# sheet.net
KiCad netlist of a schematic drawn in Altium Designer
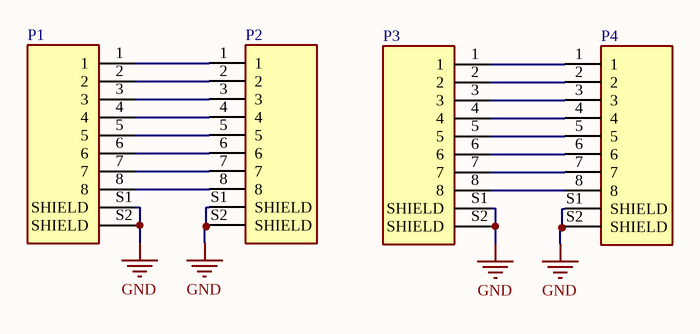
[diagram p0: sheet.SchDoc]

(export (version "E")
  (design (tool "Eeschema 10.0.6"))
  (components
    (comp (ref "P1")
      (value "1-406541-5")
      (footprint "TE_1-406541-5")
      (description "Conn RJ-45 F 8 POS 2.04mm Solder RA Thru-Hole 8 Terminal 1 Port Cat 5 Box/Tray")
      (fields (field (name "MF") "{'manufacturer': u'TE Connectivity'}"))
      (libsource (lib "1-406541-5") (part "1-406541-5"))
    )
    (comp (ref "P2")
      (value "1-406541-5")
      (footprint "TE_1-406541-5")
      (description "Conn RJ-45 F 8 POS 2.04mm Solder RA Thru-Hole 8 Terminal 1 Port Cat 5 Box/Tray")
      (fields (field (name "MF") "{'manufacturer': u'TE Connectivity'}"))
      (libsource (lib "") (part "1-406541-5_1"))
    )
    (comp (ref "P3")
      (value "1-406541-5")
      (footprint "TE_1-406541-5")
      (description "Conn RJ-45 F 8 POS 2.04mm Solder RA Thru-Hole 8 Terminal 1 Port Cat 5 Box/Tray")
      (fields (field (name "MF") "{'manufacturer': u'TE Connectivity'}"))
      (libsource (lib "1-406541-5") (part "1-406541-5"))
    )
    (comp (ref "P4")
      (value "1-406541-5")
      (footprint "TE_1-406541-5")
      (description "Conn RJ-45 F 8 POS 2.04mm Solder RA Thru-Hole 8 Terminal 1 Port Cat 5 Box/Tray")
      (fields (field (name "MF") "{'manufacturer': u'TE Connectivity'}"))
      (libsource (lib "") (part "1-406541-5_1"))
    )
  )
  (nets
    (net (code "1") (name "GND") (class "Default")
      (node (ref "P1") (pin "S1") (pinfunction "SHIELD_S1") (pintype "passive"))
      (node (ref "P1") (pin "S2") (pinfunction "SHIELD_S2") (pintype "passive"))
      (node (ref "P2") (pin "S1") (pinfunction "SHIELD_S1") (pintype "passive"))
      (node (ref "P2") (pin "S2") (pinfunction "SHIELD_S2") (pintype "passive"))
      (node (ref "P3") (pin "S1") (pinfunction "SHIELD_S1") (pintype "passive"))
      (node (ref "P3") (pin "S2") (pinfunction "SHIELD_S2") (pintype "passive"))
      (node (ref "P4") (pin "S1") (pinfunction "SHIELD_S1") (pintype "passive"))
      (node (ref "P4") (pin "S2") (pinfunction "SHIELD_S2") (pintype "passive"))
    )
    (net (code "2") (name "Net-(P1-Pad1)") (class "Default")
      (node (ref "P1") (pin "1") (pinfunction "1_1") (pintype "passive"))
      (node (ref "P2") (pin "1") (pinfunction "1_1") (pintype "passive"))
    )
    (net (code "3") (name "Net-(P1-Pad2)") (class "Default")
      (node (ref "P1") (pin "2") (pinfunction "2_2") (pintype "passive"))
      (node (ref "P2") (pin "2") (pinfunction "2_2") (pintype "passive"))
    )
    (net (code "4") (name "Net-(P1-Pad3)") (class "Default")
      (node (ref "P1") (pin "3") (pinfunction "3_3") (pintype "passive"))
      (node (ref "P2") (pin "3") (pinfunction "3_3") (pintype "passive"))
    )
    (net (code "5") (name "Net-(P1-Pad4)") (class "Default")
      (node (ref "P1") (pin "4") (pinfunction "4_4") (pintype "passive"))
      (node (ref "P2") (pin "4") (pinfunction "4_4") (pintype "passive"))
    )
    (net (code "6") (name "Net-(P1-Pad5)") (class "Default")
      (node (ref "P1") (pin "5") (pinfunction "5_5") (pintype "passive"))
      (node (ref "P2") (pin "5") (pinfunction "5_5") (pintype "passive"))
    )
    (net (code "7") (name "Net-(P1-Pad6)") (class "Default")
      (node (ref "P1") (pin "6") (pinfunction "6_6") (pintype "passive"))
      (node (ref "P2") (pin "6") (pinfunction "6_6") (pintype "passive"))
    )
    (net (code "8") (name "Net-(P1-Pad7)") (class "Default")
      (node (ref "P1") (pin "7") (pinfunction "7_7") (pintype "passive"))
      (node (ref "P2") (pin "7") (pinfunction "7_7") (pintype "passive"))
    )
    (net (code "9") (name "Net-(P1-Pad8)") (class "Default")
      (node (ref "P1") (pin "8") (pinfunction "8_8") (pintype "passive"))
      (node (ref "P2") (pin "8") (pinfunction "8_8") (pintype "passive"))
    )
    (net (code "10") (name "Net-(P3-Pad1)") (class "Default")
      (node (ref "P3") (pin "1") (pinfunction "1_1") (pintype "passive"))
      (node (ref "P4") (pin "1") (pinfunction "1_1") (pintype "passive"))
    )
    (net (code "11") (name "Net-(P3-Pad2)") (class "Default")
      (node (ref "P3") (pin "2") (pinfunction "2_2") (pintype "passive"))
      (node (ref "P4") (pin "2") (pinfunction "2_2") (pintype "passive"))
    )
    (net (code "12") (name "Net-(P3-Pad3)") (class "Default")
      (node (ref "P3") (pin "3") (pinfunction "3_3") (pintype "passive"))
      (node (ref "P4") (pin "3") (pinfunction "3_3") (pintype "passive"))
    )
    (net (code "13") (name "Net-(P3-Pad4)") (class "Default")
      (node (ref "P3") (pin "4") (pinfunction "4_4") (pintype "passive"))
      (node (ref "P4") (pin "4") (pinfunction "4_4") (pintype "passive"))
    )
    (net (code "14") (name "Net-(P3-Pad5)") (class "Default")
      (node (ref "P3") (pin "5") (pinfunction "5_5") (pintype "passive"))
      (node (ref "P4") (pin "5") (pinfunction "5_5") (pintype "passive"))
    )
    (net (code "15") (name "Net-(P3-Pad6)") (class "Default")
      (node (ref "P3") (pin "6") (pinfunction "6_6") (pintype "passive"))
      (node (ref "P4") (pin "6") (pinfunction "6_6") (pintype "passive"))
    )
    (net (code "16") (name "Net-(P3-Pad7)") (class "Default")
      (node (ref "P3") (pin "7") (pinfunction "7_7") (pintype "passive"))
      (node (ref "P4") (pin "7") (pinfunction "7_7") (pintype "passive"))
    )
    (net (code "17") (name "Net-(P3-Pad8)") (class "Default")
      (node (ref "P3") (pin "8") (pinfunction "8_8") (pintype "passive"))
      (node (ref "P4") (pin "8") (pinfunction "8_8") (pintype "passive"))
    )
  )
)
